# stm32f072-breakout.net
KiCad netlist of a schematic drawn in EAGLE
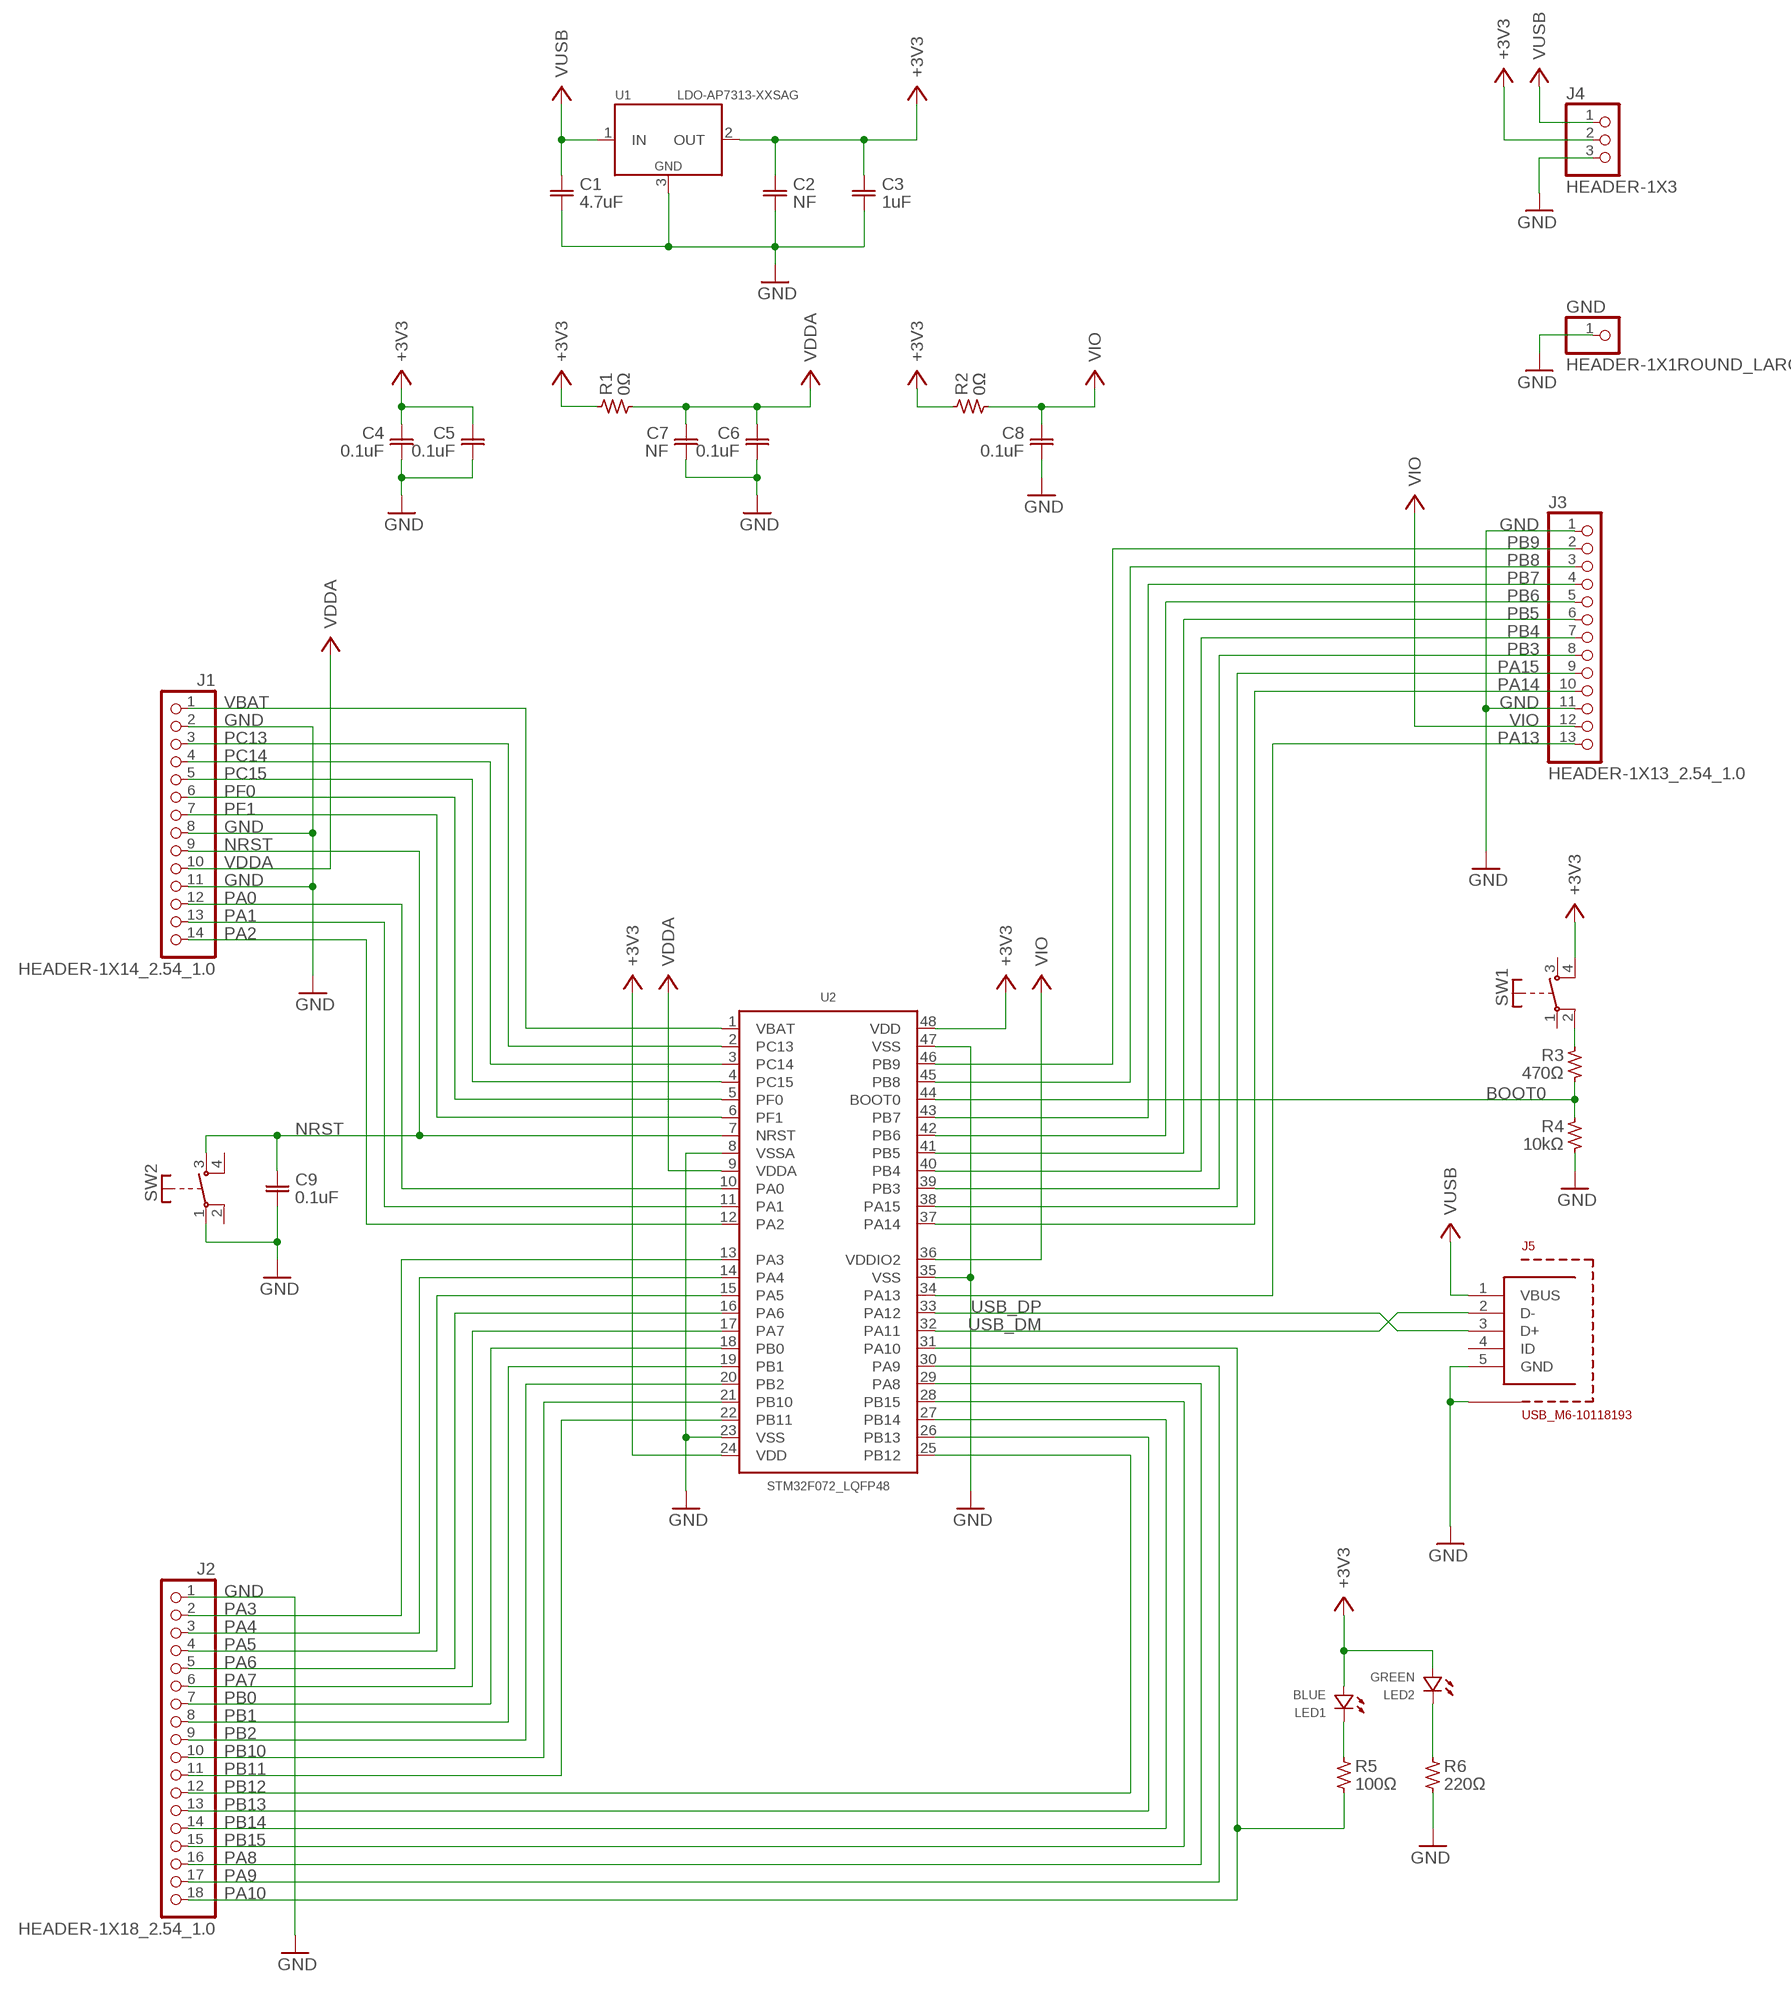
[diagram p0: schematic, sheet 1]

(export (version "E")
  (design (tool "Eeschema 10.0.6"))
  (components
    (comp (ref "C1")
      (value "4.7uF")
      (footprint "eagle-import:0603")
      (libsource (lib "eagle-import") (part "C-EU-0603"))
    )
    (comp (ref "C2")
      (value "NF")
      (footprint "eagle-import:0603")
      (libsource (lib "eagle-import") (part "C-EU-0603"))
    )
    (comp (ref "C3")
      (value "1uF")
      (footprint "eagle-import:0603")
      (libsource (lib "eagle-import") (part "C-EU-0603"))
    )
    (comp (ref "C4")
      (value "0.1uF")
      (footprint "eagle-import:0603")
      (libsource (lib "eagle-import") (part "C-EU-0603"))
    )
    (comp (ref "C5")
      (value "0.1uF")
      (footprint "eagle-import:0603")
      (libsource (lib "eagle-import") (part "C-EU-0603"))
    )
    (comp (ref "C6")
      (value "0.1uF")
      (footprint "eagle-import:0603")
      (libsource (lib "eagle-import") (part "C-EU-0603"))
    )
    (comp (ref "C7")
      (value "NF")
      (footprint "eagle-import:0603")
      (libsource (lib "eagle-import") (part "C-EU-0603"))
    )
    (comp (ref "C8")
      (value "0.1uF")
      (footprint "eagle-import:0603")
      (libsource (lib "eagle-import") (part "C-EU-0603"))
    )
    (comp (ref "C9")
      (value "0.1uF")
      (footprint "eagle-import:0603")
      (libsource (lib "eagle-import") (part "C-EU-0603"))
    )
    (comp (ref "GND")
      (value "HEADER-1X1ROUND_LARGE")
      (footprint "eagle-import:1X01_ROUND_LARGE")
      (libsource (lib "eagle-import") (part "HEADER-1X1ROUND_LARGE"))
    )
    (comp (ref "J1")
      (value "HEADER-1X14_2.54_1.0")
      (footprint "eagle-import:1X14_OVAL")
      (libsource (lib "eagle-import") (part "HEADER-1X14_2.54_1.0"))
    )
    (comp (ref "J2")
      (value "HEADER-1X18_2.54_1.0")
      (footprint "eagle-import:1X18_OVAL")
      (libsource (lib "eagle-import") (part "HEADER-1X18_2.54_1.0"))
    )
    (comp (ref "J3")
      (value "HEADER-1X13_2.54_1.0")
      (footprint "eagle-import:1X13_OVAL")
      (libsource (lib "eagle-import") (part "HEADER-1X13_2.54_1.0"))
    )
    (comp (ref "J4")
      (value "HEADER-1X3")
      (footprint "eagle-import:1X03_OVAL")
      (libsource (lib "eagle-import") (part "HEADER-1X3"))
    )
    (comp (ref "J5")
      (value "USB_M6-10118193")
      (footprint "eagle-import:FCI-10118193")
      (libsource (lib "eagle-import") (part "USB_M6-10118193"))
    )
    (comp (ref "LED1")
      (value "BLUE")
      (footprint "eagle-import:0603-POL")
      (libsource (lib "eagle-import") (part "LED"))
    )
    (comp (ref "LED2")
      (value "GREEN")
      (footprint "eagle-import:0603-POL")
      (libsource (lib "eagle-import") (part "LED"))
    )
    (comp (ref "R1")
      (value "0Ω")
      (footprint "eagle-import:0603")
      (libsource (lib "eagle-import") (part "R-US-0603"))
    )
    (comp (ref "R2")
      (value "0Ω")
      (footprint "eagle-import:0603")
      (libsource (lib "eagle-import") (part "R-US-0603"))
    )
    (comp (ref "R3")
      (value "470Ω")
      (footprint "eagle-import:0603")
      (libsource (lib "eagle-import") (part "R-US-0603"))
    )
    (comp (ref "R4")
      (value "10kΩ")
      (footprint "eagle-import:0603")
      (libsource (lib "eagle-import") (part "R-US-0603"))
    )
    (comp (ref "R5")
      (value "100Ω")
      (footprint "eagle-import:0603")
      (libsource (lib "eagle-import") (part "R-US-0603"))
    )
    (comp (ref "R6")
      (value "220Ω")
      (footprint "eagle-import:0603")
      (libsource (lib "eagle-import") (part "R-US-0603"))
    )
    (comp (ref "SW1")
      (value "SWITCH_OFF(ON)_2-MJTP1140A")
      (footprint "eagle-import:MJTP1140A")
      (libsource (lib "eagle-import") (part "SWITCH_OFF(ON)_2-MJTP1140A"))
    )
    (comp (ref "SW2")
      (value "SWITCH_OFF(ON)_2-MJTP1140A")
      (footprint "eagle-import:MJTP1140A")
      (libsource (lib "eagle-import") (part "SWITCH_OFF(ON)_2-MJTP1140A"))
    )
    (comp (ref "U1")
      (value "LDO-AP7313-XXSAG")
      (footprint "eagle-import:SOT23")
      (libsource (lib "eagle-import") (part "LDO-AP7313-XXSAG"))
    )
    (comp (ref "U2")
      (value "STM32F072_LQFP48")
      (footprint "eagle-import:LQFP48")
      (libsource (lib "eagle-import") (part "STM32F072_LQFP48"))
    )
  )
  (nets
    (net (code "1") (name "+3V3") (class "Default")
      (node (ref "C2") (pin "1") (pinfunction "1_1") (pintype "passive"))
      (node (ref "C3") (pin "1") (pinfunction "1_1") (pintype "passive"))
      (node (ref "C4") (pin "1") (pinfunction "1_1") (pintype "passive"))
      (node (ref "C5") (pin "1") (pinfunction "1_1") (pintype "passive"))
      (node (ref "J4") (pin "2") (pinfunction "2_2") (pintype "passive"))
      (node (ref "LED1") (pin "2") (pinfunction "A_2") (pintype "bidirectional"))
      (node (ref "LED2") (pin "2") (pinfunction "A_2") (pintype "bidirectional"))
      (node (ref "R1") (pin "1") (pinfunction "1_1") (pintype "passive"))
      (node (ref "R2") (pin "1") (pinfunction "1_1") (pintype "passive"))
      (node (ref "SW1") (pin "4") (pinfunction "4_4") (pintype "passive"))
      (node (ref "U1") (pin "2") (pinfunction "OUT_2") (pintype "bidirectional"))
      (node (ref "U2") (pin "24") (pinfunction "VDD_24") (pintype "bidirectional"))
      (node (ref "U2") (pin "48") (pinfunction "VDD_48") (pintype "bidirectional"))
    )
    (net (code "2") (name "/BOOT0") (class "Default")
      (node (ref "R3") (pin "2") (pinfunction "2_2") (pintype "passive"))
      (node (ref "R4") (pin "1") (pinfunction "1_1") (pintype "passive"))
      (node (ref "U2") (pin "44") (pinfunction "BOOT0_44") (pintype "bidirectional"))
    )
    (net (code "3") (name "/NRST") (class "Default")
      (node (ref "C9") (pin "1") (pinfunction "1_1") (pintype "passive"))
      (node (ref "J1") (pin "9") (pinfunction "9_9") (pintype "passive"))
      (node (ref "SW2") (pin "3") (pinfunction "3_3") (pintype "passive"))
      (node (ref "U2") (pin "7") (pinfunction "NRST_7") (pintype "bidirectional"))
    )
    (net (code "4") (name "/PA0") (class "Default")
      (node (ref "J1") (pin "12") (pinfunction "12_12") (pintype "passive"))
      (node (ref "U2") (pin "10") (pinfunction "PA0_10") (pintype "bidirectional"))
    )
    (net (code "5") (name "/PA1") (class "Default")
      (node (ref "J1") (pin "13") (pinfunction "13_13") (pintype "passive"))
      (node (ref "U2") (pin "11") (pinfunction "PA1_11") (pintype "bidirectional"))
    )
    (net (code "6") (name "/PA2") (class "Default")
      (node (ref "J1") (pin "14") (pinfunction "14_14") (pintype "passive"))
      (node (ref "U2") (pin "12") (pinfunction "PA2_12") (pintype "bidirectional"))
    )
    (net (code "7") (name "/PA3") (class "Default")
      (node (ref "J2") (pin "2") (pinfunction "2_2") (pintype "passive"))
      (node (ref "U2") (pin "13") (pinfunction "PA3_13") (pintype "bidirectional"))
    )
    (net (code "8") (name "/PA4") (class "Default")
      (node (ref "J2") (pin "3") (pinfunction "3_3") (pintype "passive"))
      (node (ref "U2") (pin "14") (pinfunction "PA4_14") (pintype "bidirectional"))
    )
    (net (code "9") (name "/PA5") (class "Default")
      (node (ref "J2") (pin "4") (pinfunction "4_4") (pintype "passive"))
      (node (ref "U2") (pin "15") (pinfunction "PA5_15") (pintype "bidirectional"))
    )
    (net (code "10") (name "/PA6") (class "Default")
      (node (ref "J2") (pin "5") (pinfunction "5_5") (pintype "passive"))
      (node (ref "U2") (pin "16") (pinfunction "PA6_16") (pintype "bidirectional"))
    )
    (net (code "11") (name "/PA7") (class "Default")
      (node (ref "J2") (pin "6") (pinfunction "6_6") (pintype "passive"))
      (node (ref "U2") (pin "17") (pinfunction "PA7_17") (pintype "bidirectional"))
    )
    (net (code "12") (name "/PA8") (class "Default")
      (node (ref "J2") (pin "16") (pinfunction "16_16") (pintype "passive"))
      (node (ref "U2") (pin "29") (pinfunction "PA8_29") (pintype "bidirectional"))
    )
    (net (code "13") (name "/PA9") (class "Default")
      (node (ref "J2") (pin "17") (pinfunction "17_17") (pintype "passive"))
      (node (ref "U2") (pin "30") (pinfunction "PA9_30") (pintype "bidirectional"))
    )
    (net (code "14") (name "/PA10") (class "Default")
      (node (ref "J2") (pin "18") (pinfunction "18_18") (pintype "passive"))
      (node (ref "R5") (pin "2") (pinfunction "2_2") (pintype "passive"))
      (node (ref "U2") (pin "31") (pinfunction "PA10_31") (pintype "bidirectional"))
    )
    (net (code "15") (name "/PA13") (class "Default")
      (node (ref "J3") (pin "13") (pinfunction "13_13") (pintype "passive"))
      (node (ref "U2") (pin "34") (pinfunction "PA13_34") (pintype "bidirectional"))
    )
    (net (code "16") (name "/PA14") (class "Default")
      (node (ref "J3") (pin "10") (pinfunction "10_10") (pintype "passive"))
      (node (ref "U2") (pin "37") (pinfunction "PA14_37") (pintype "bidirectional"))
    )
    (net (code "17") (name "/PA15") (class "Default")
      (node (ref "J3") (pin "9") (pinfunction "9_9") (pintype "passive"))
      (node (ref "U2") (pin "38") (pinfunction "PA15_38") (pintype "bidirectional"))
    )
    (net (code "18") (name "/PB0") (class "Default")
      (node (ref "J2") (pin "7") (pinfunction "7_7") (pintype "passive"))
      (node (ref "U2") (pin "18") (pinfunction "PB0_18") (pintype "bidirectional"))
    )
    (net (code "19") (name "/PB1") (class "Default")
      (node (ref "J2") (pin "8") (pinfunction "8_8") (pintype "passive"))
      (node (ref "U2") (pin "19") (pinfunction "PB1_19") (pintype "bidirectional"))
    )
    (net (code "20") (name "/PB2") (class "Default")
      (node (ref "J2") (pin "9") (pinfunction "9_9") (pintype "passive"))
      (node (ref "U2") (pin "20") (pinfunction "PB2_20") (pintype "bidirectional"))
    )
    (net (code "21") (name "/PB3") (class "Default")
      (node (ref "J3") (pin "8") (pinfunction "8_8") (pintype "passive"))
      (node (ref "U2") (pin "39") (pinfunction "PB3_39") (pintype "bidirectional"))
    )
    (net (code "22") (name "/PB4") (class "Default")
      (node (ref "J3") (pin "7") (pinfunction "7_7") (pintype "passive"))
      (node (ref "U2") (pin "40") (pinfunction "PB4_40") (pintype "bidirectional"))
    )
    (net (code "23") (name "/PB5") (class "Default")
      (node (ref "J3") (pin "6") (pinfunction "6_6") (pintype "passive"))
      (node (ref "U2") (pin "41") (pinfunction "PB5_41") (pintype "bidirectional"))
    )
    (net (code "24") (name "/PB6") (class "Default")
      (node (ref "J3") (pin "5") (pinfunction "5_5") (pintype "passive"))
      (node (ref "U2") (pin "42") (pinfunction "PB6_42") (pintype "bidirectional"))
    )
    (net (code "25") (name "/PB7") (class "Default")
      (node (ref "J3") (pin "4") (pinfunction "4_4") (pintype "passive"))
      (node (ref "U2") (pin "43") (pinfunction "PB7_43") (pintype "bidirectional"))
    )
    (net (code "26") (name "/PB8") (class "Default")
      (node (ref "J3") (pin "3") (pinfunction "3_3") (pintype "passive"))
      (node (ref "U2") (pin "45") (pinfunction "PB8_45") (pintype "bidirectional"))
    )
    (net (code "27") (name "/PB9") (class "Default")
      (node (ref "J3") (pin "2") (pinfunction "2_2") (pintype "passive"))
      (node (ref "U2") (pin "46") (pinfunction "PB9_46") (pintype "bidirectional"))
    )
    (net (code "28") (name "/PB10") (class "Default")
      (node (ref "J2") (pin "10") (pinfunction "10_10") (pintype "passive"))
      (node (ref "U2") (pin "21") (pinfunction "PB10_21") (pintype "bidirectional"))
    )
    (net (code "29") (name "/PB11") (class "Default")
      (node (ref "J2") (pin "11") (pinfunction "11_11") (pintype "passive"))
      (node (ref "U2") (pin "22") (pinfunction "PB11_22") (pintype "bidirectional"))
    )
    (net (code "30") (name "/PB12") (class "Default")
      (node (ref "J2") (pin "12") (pinfunction "12_12") (pintype "passive"))
      (node (ref "U2") (pin "25") (pinfunction "PB12_25") (pintype "bidirectional"))
    )
    (net (code "31") (name "/PB13") (class "Default")
      (node (ref "J2") (pin "13") (pinfunction "13_13") (pintype "passive"))
      (node (ref "U2") (pin "26") (pinfunction "PB13_26") (pintype "bidirectional"))
    )
    (net (code "32") (name "/PB14") (class "Default")
      (node (ref "J2") (pin "14") (pinfunction "14_14") (pintype "passive"))
      (node (ref "U2") (pin "27") (pinfunction "PB14_27") (pintype "bidirectional"))
    )
    (net (code "33") (name "/PB15") (class "Default")
      (node (ref "J2") (pin "15") (pinfunction "15_15") (pintype "passive"))
      (node (ref "U2") (pin "28") (pinfunction "PB15_28") (pintype "bidirectional"))
    )
    (net (code "34") (name "/PC13") (class "Default")
      (node (ref "J1") (pin "3") (pinfunction "3_3") (pintype "passive"))
      (node (ref "U2") (pin "2") (pinfunction "PC13_2") (pintype "bidirectional"))
    )
    (net (code "35") (name "/PC14") (class "Default")
      (node (ref "J1") (pin "4") (pinfunction "4_4") (pintype "passive"))
      (node (ref "U2") (pin "3") (pinfunction "PC14_3") (pintype "bidirectional"))
    )
    (net (code "36") (name "/PC15") (class "Default")
      (node (ref "J1") (pin "5") (pinfunction "5_5") (pintype "passive"))
      (node (ref "U2") (pin "4") (pinfunction "PC15_4") (pintype "bidirectional"))
    )
    (net (code "37") (name "/PF0") (class "Default")
      (node (ref "J1") (pin "6") (pinfunction "6_6") (pintype "passive"))
      (node (ref "U2") (pin "5") (pinfunction "PF0_5") (pintype "bidirectional"))
    )
    (net (code "38") (name "/PF1") (class "Default")
      (node (ref "J1") (pin "7") (pinfunction "7_7") (pintype "passive"))
      (node (ref "U2") (pin "6") (pinfunction "PF1_6") (pintype "bidirectional"))
    )
    (net (code "39") (name "/USB_DM") (class "Default")
      (node (ref "J5") (pin "2") (pinfunction "D-_2") (pintype "bidirectional"))
      (node (ref "U2") (pin "32") (pinfunction "PA11_32") (pintype "bidirectional"))
    )
    (net (code "40") (name "/USB_DP") (class "Default")
      (node (ref "J5") (pin "3") (pinfunction "D+_3") (pintype "bidirectional"))
      (node (ref "U2") (pin "33") (pinfunction "PA12_33") (pintype "bidirectional"))
    )
    (net (code "41") (name "/VBAT") (class "Default")
      (node (ref "J1") (pin "1") (pinfunction "1_1") (pintype "passive"))
      (node (ref "U2") (pin "1") (pinfunction "VBAT_1") (pintype "bidirectional"))
    )
    (net (code "42") (name "GND") (class "Default")
      (node (ref "C1") (pin "2") (pinfunction "2_2") (pintype "passive"))
      (node (ref "C2") (pin "2") (pinfunction "2_2") (pintype "passive"))
      (node (ref "C3") (pin "2") (pinfunction "2_2") (pintype "passive"))
      (node (ref "C4") (pin "2") (pinfunction "2_2") (pintype "passive"))
      (node (ref "C5") (pin "2") (pinfunction "2_2") (pintype "passive"))
      (node (ref "C6") (pin "2") (pinfunction "2_2") (pintype "passive"))
      (node (ref "C7") (pin "2") (pinfunction "2_2") (pintype "passive"))
      (node (ref "C8") (pin "2") (pinfunction "2_2") (pintype "passive"))
      (node (ref "C9") (pin "2") (pinfunction "2_2") (pintype "passive"))
      (node (ref "GND") (pin "1") (pinfunction "1_1") (pintype "passive"))
      (node (ref "J1") (pin "11") (pinfunction "11_11") (pintype "passive"))
      (node (ref "J1") (pin "2") (pinfunction "2_2") (pintype "passive"))
      (node (ref "J1") (pin "8") (pinfunction "8_8") (pintype "passive"))
      (node (ref "J2") (pin "1") (pinfunction "1_1") (pintype "passive"))
      (node (ref "J3") (pin "1") (pinfunction "1_1") (pintype "passive"))
      (node (ref "J3") (pin "11") (pinfunction "11_11") (pintype "passive"))
      (node (ref "J4") (pin "3") (pinfunction "3_3") (pintype "passive"))
      (node (ref "J5") (pin "5") (pinfunction "GND_5") (pintype "bidirectional"))
      (node (ref "J5") (pin "SHIELD@1") (pinfunction "SHIELD_SHIELD@1") (pintype "bidirectional"))
      (node (ref "J5") (pin "SHIELD@2") (pinfunction "SHIELD_SHIELD@2") (pintype "bidirectional"))
      (node (ref "J5") (pin "SHIELD@3") (pinfunction "SHIELD_SHIELD@3") (pintype "bidirectional"))
      (node (ref "J5") (pin "SHIELD@4") (pinfunction "SHIELD_SHIELD@4") (pintype "bidirectional"))
      (node (ref "J5") (pin "SHIELD@5") (pinfunction "SHIELD_SHIELD@5") (pintype "bidirectional"))
      (node (ref "J5") (pin "SHIELD@6") (pinfunction "SHIELD_SHIELD@6") (pintype "bidirectional"))
      (node (ref "J5") (pin "SHIELD@7") (pinfunction "SHIELD_SHIELD@7") (pintype "bidirectional"))
      (node (ref "J5") (pin "SHIELD@8") (pinfunction "SHIELD_SHIELD@8") (pintype "bidirectional"))
      (node (ref "R4") (pin "2") (pinfunction "2_2") (pintype "passive"))
      (node (ref "R6") (pin "2") (pinfunction "2_2") (pintype "passive"))
      (node (ref "SW2") (pin "1") (pinfunction "1_1") (pintype "passive"))
      (node (ref "U1") (pin "3") (pinfunction "GND_3") (pintype "bidirectional"))
      (node (ref "U2") (pin "23") (pinfunction "VSS_23") (pintype "bidirectional"))
      (node (ref "U2") (pin "35") (pinfunction "VSS_35") (pintype "bidirectional"))
      (node (ref "U2") (pin "47") (pinfunction "VSS_47") (pintype "bidirectional"))
      (node (ref "U2") (pin "8") (pinfunction "VSSA_8") (pintype "bidirectional"))
    )
    (net (code "43") (name "Net-(LED1-C)") (class "Default")
      (node (ref "LED1") (pin "1") (pinfunction "C_1") (pintype "bidirectional"))
      (node (ref "R5") (pin "1") (pinfunction "1_1") (pintype "passive"))
    )
    (net (code "44") (name "Net-(LED2-C)") (class "Default")
      (node (ref "LED2") (pin "1") (pinfunction "C_1") (pintype "bidirectional"))
      (node (ref "R6") (pin "1") (pinfunction "1_1") (pintype "passive"))
    )
    (net (code "45") (name "Net-(R3-Pad1)") (class "Default")
      (node (ref "R3") (pin "1") (pinfunction "1_1") (pintype "passive"))
      (node (ref "SW1") (pin "2") (pinfunction "2_2") (pintype "passive"))
    )
    (net (code "46") (name "VDDA") (class "Default")
      (node (ref "C6") (pin "1") (pinfunction "1_1") (pintype "passive"))
      (node (ref "C7") (pin "1") (pinfunction "1_1") (pintype "passive"))
      (node (ref "J1") (pin "10") (pinfunction "10_10") (pintype "passive"))
      (node (ref "R1") (pin "2") (pinfunction "2_2") (pintype "passive"))
      (node (ref "U2") (pin "9") (pinfunction "VDDA_9") (pintype "bidirectional"))
    )
    (net (code "47") (name "VIO") (class "Default")
      (node (ref "C8") (pin "1") (pinfunction "1_1") (pintype "passive"))
      (node (ref "J3") (pin "12") (pinfunction "12_12") (pintype "passive"))
      (node (ref "R2") (pin "2") (pinfunction "2_2") (pintype "passive"))
      (node (ref "U2") (pin "36") (pinfunction "VDDIO2_36") (pintype "bidirectional"))
    )
    (net (code "48") (name "VUSB") (class "Default")
      (node (ref "C1") (pin "1") (pinfunction "1_1") (pintype "passive"))
      (node (ref "J4") (pin "1") (pinfunction "1_1") (pintype "passive"))
      (node (ref "J5") (pin "1") (pinfunction "VBUS_1") (pintype "bidirectional"))
      (node (ref "U1") (pin "1") (pinfunction "IN_1") (pintype "bidirectional"))
    )
    (net (code "49") (name "unconnected-(J5-ID-Pad4)") (class "Default")
      (node (ref "J5") (pin "4") (pinfunction "ID_4") (pintype "bidirectional"))
    )
    (net (code "50") (name "unconnected-(SW1-Pad1)") (class "Default")
      (node (ref "SW1") (pin "1") (pinfunction "1_1") (pintype "passive"))
    )
    (net (code "51") (name "unconnected-(SW1-Pad3)") (class "Default")
      (node (ref "SW1") (pin "3") (pinfunction "3_3") (pintype "passive"))
    )
    (net (code "52") (name "unconnected-(SW2-Pad2)") (class "Default")
      (node (ref "SW2") (pin "2") (pinfunction "2_2") (pintype "passive"))
    )
    (net (code "53") (name "unconnected-(SW2-Pad4)") (class "Default")
      (node (ref "SW2") (pin "4") (pinfunction "4_4") (pintype "passive"))
    )
  )
)
